# RSS_0_3.net
KiCad netlist of a schematic drawn in EAGLE
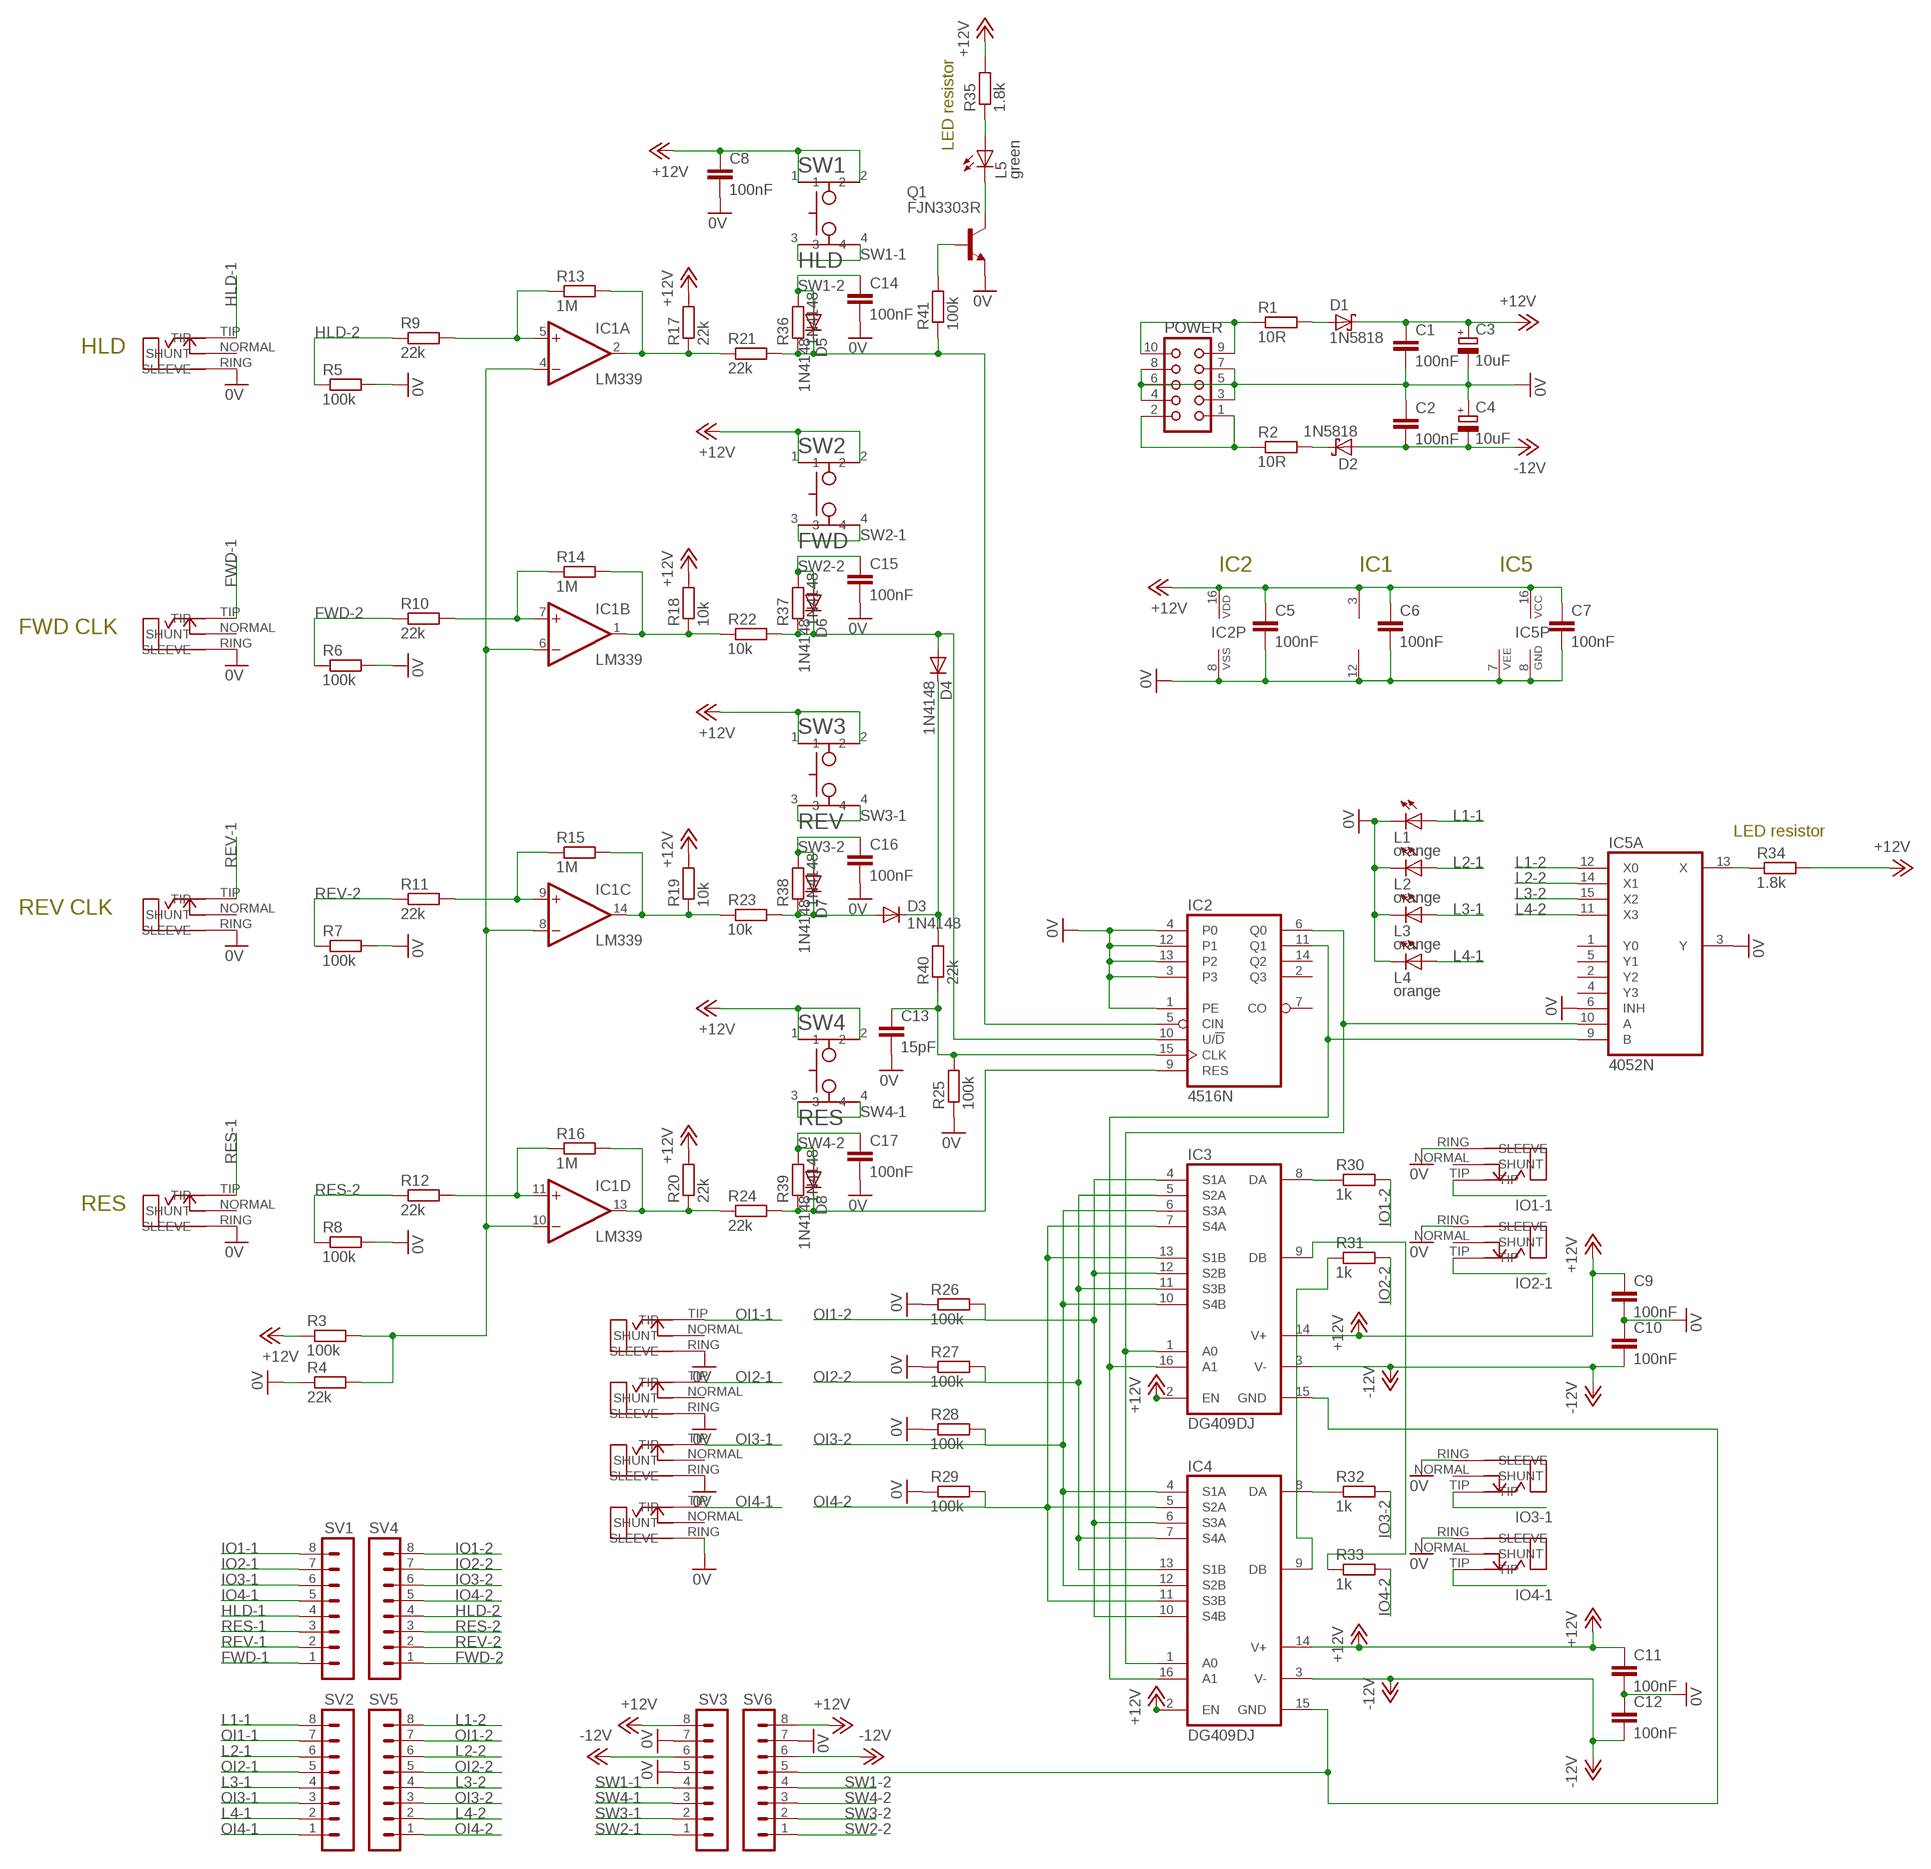
[diagram p0: schematic, sheet 1]

(export (version "E")
  (design (tool "Eeschema 10.0.6"))
  (components
    (comp (ref "C1")
      (value "100nF")
      (footprint "eagle-import:C025-024X044")
      (libsource (lib "eagle-import") (part "C-EU025-024X044"))
    )
    (comp (ref "C2")
      (value "100nF")
      (footprint "eagle-import:C025-024X044")
      (libsource (lib "eagle-import") (part "C-EU025-024X044"))
    )
    (comp (ref "C3")
      (value "10uF")
      (footprint "eagle-import:E2-5")
      (libsource (lib "eagle-import") (part "CPOL-EUE2-5"))
    )
    (comp (ref "C4")
      (value "10uF")
      (footprint "eagle-import:E2-5")
      (libsource (lib "eagle-import") (part "CPOL-EUE2-5"))
    )
    (comp (ref "C5")
      (value "100nF")
      (footprint "eagle-import:C025-024X044")
      (libsource (lib "eagle-import") (part "C-EU025-024X044"))
    )
    (comp (ref "C6")
      (value "100nF")
      (footprint "eagle-import:C025-024X044")
      (libsource (lib "eagle-import") (part "C-EU025-024X044"))
    )
    (comp (ref "C7")
      (value "100nF")
      (footprint "eagle-import:C025-024X044")
      (libsource (lib "eagle-import") (part "C-EU025-024X044"))
    )
    (comp (ref "C8")
      (value "100nF")
      (footprint "eagle-import:C025-024X044")
      (libsource (lib "eagle-import") (part "C-EU025-024X044"))
    )
    (comp (ref "C9")
      (value "100nF")
      (footprint "eagle-import:C025-024X044")
      (libsource (lib "eagle-import") (part "C-EU025-024X044"))
    )
    (comp (ref "C10")
      (value "100nF")
      (footprint "eagle-import:C025-024X044")
      (libsource (lib "eagle-import") (part "C-EU025-024X044"))
    )
    (comp (ref "C11")
      (value "100nF")
      (footprint "eagle-import:C025-024X044")
      (libsource (lib "eagle-import") (part "C-EU025-024X044"))
    )
    (comp (ref "C12")
      (value "100nF")
      (footprint "eagle-import:C025-024X044")
      (libsource (lib "eagle-import") (part "C-EU025-024X044"))
    )
    (comp (ref "C13")
      (value "15pF")
      (footprint "eagle-import:C025-024X044")
      (libsource (lib "eagle-import") (part "C-EU025-024X044"))
    )
    (comp (ref "C14")
      (value "100nF")
      (footprint "eagle-import:C025-024X044")
      (libsource (lib "eagle-import") (part "C-EU025-024X044"))
    )
    (comp (ref "C15")
      (value "100nF")
      (footprint "eagle-import:C025-024X044")
      (libsource (lib "eagle-import") (part "C-EU025-024X044"))
    )
    (comp (ref "C16")
      (value "100nF")
      (footprint "eagle-import:C025-024X044")
      (libsource (lib "eagle-import") (part "C-EU025-024X044"))
    )
    (comp (ref "C17")
      (value "100nF")
      (footprint "eagle-import:C025-024X044")
      (libsource (lib "eagle-import") (part "C-EU025-024X044"))
    )
    (comp (ref "D1")
      (value "1N5818")
      (footprint "eagle-import:DO41-7")
      (libsource (lib "eagle-import") (part "SB130DO-204AL"))
    )
    (comp (ref "D2")
      (value "1N5818")
      (footprint "eagle-import:DO41-7")
      (libsource (lib "eagle-import") (part "SB130DO-204AL"))
    )
    (comp (ref "D3")
      (value "1N4148")
      (footprint "eagle-import:DO35-7")
      (libsource (lib "eagle-import") (part "1N4148DO35-7"))
    )
    (comp (ref "D4")
      (value "1N4148")
      (footprint "eagle-import:DO35-7")
      (libsource (lib "eagle-import") (part "1N4148DO35-7"))
    )
    (comp (ref "D5")
      (value "1N4148")
      (footprint "eagle-import:DO35-7")
      (libsource (lib "eagle-import") (part "1N4148DO35-7"))
    )
    (comp (ref "D6")
      (value "1N4148")
      (footprint "eagle-import:DO35-7")
      (libsource (lib "eagle-import") (part "1N4148DO35-7"))
    )
    (comp (ref "D7")
      (value "1N4148")
      (footprint "eagle-import:DO35-7")
      (libsource (lib "eagle-import") (part "1N4148DO35-7"))
    )
    (comp (ref "D8")
      (value "1N4148")
      (footprint "eagle-import:DO35-7")
      (libsource (lib "eagle-import") (part "1N4148DO35-7"))
    )
    (comp (ref "FWD")
      (value "ERTHENVAR_3.5MM_JACK")
      (footprint "eagle-import:THONKICON")
      (libsource (lib "eagle-import") (part "ERTHENVAR_3.5MM_JACK"))
    )
    (comp (ref "HLD")
      (value "ERTHENVAR_3.5MM_JACK")
      (footprint "eagle-import:THONKICON")
      (libsource (lib "eagle-import") (part "ERTHENVAR_3.5MM_JACK"))
    )
    (comp (ref "I/O1")
      (value "ERTHENVAR_3.5MM_JACK")
      (footprint "eagle-import:THONKICON")
      (libsource (lib "eagle-import") (part "ERTHENVAR_3.5MM_JACK"))
    )
    (comp (ref "I/O2")
      (value "ERTHENVAR_3.5MM_JACK")
      (footprint "eagle-import:THONKICON")
      (libsource (lib "eagle-import") (part "ERTHENVAR_3.5MM_JACK"))
    )
    (comp (ref "I/O3")
      (value "ERTHENVAR_3.5MM_JACK")
      (footprint "eagle-import:THONKICON")
      (libsource (lib "eagle-import") (part "ERTHENVAR_3.5MM_JACK"))
    )
    (comp (ref "I/O4")
      (value "ERTHENVAR_3.5MM_JACK")
      (footprint "eagle-import:THONKICON")
      (libsource (lib "eagle-import") (part "ERTHENVAR_3.5MM_JACK"))
    )
    (comp (ref "IC1")
      (value "LM339")
      (footprint "eagle-import:DIL14")
      (libsource (lib "eagle-import") (part "LM2901N"))
    )
    (comp (ref "IC2")
      (value "4516N")
      (footprint "eagle-import:DIL16")
      (libsource (lib "eagle-import") (part "4516N"))
    )
    (comp (ref "IC3")
      (value "DG409DJ")
      (footprint "eagle-import:DIL16")
      (fields (field (name "MF") "INTERSIL"))
      (libsource (lib "eagle-import") (part "DG409DJ"))
    )
    (comp (ref "IC4")
      (value "DG409DJ")
      (footprint "eagle-import:DIL16")
      (fields (field (name "MF") "INTERSIL"))
      (libsource (lib "eagle-import") (part "DG409DJ"))
    )
    (comp (ref "IC5")
      (value "4052N")
      (footprint "eagle-import:DIL16")
      (libsource (lib "eagle-import") (part "4052N"))
    )
    (comp (ref "L1")
      (value "orange")
      (footprint "eagle-import:LED3MM")
      (libsource (lib "eagle-import") (part "LED3MM"))
    )
    (comp (ref "L2")
      (value "orange")
      (footprint "eagle-import:LED3MM")
      (libsource (lib "eagle-import") (part "LED3MM"))
    )
    (comp (ref "L3")
      (value "orange")
      (footprint "eagle-import:LED3MM")
      (libsource (lib "eagle-import") (part "LED3MM"))
    )
    (comp (ref "L4")
      (value "orange")
      (footprint "eagle-import:LED3MM")
      (libsource (lib "eagle-import") (part "LED3MM"))
    )
    (comp (ref "L5")
      (value "green")
      (footprint "eagle-import:LED3MM")
      (libsource (lib "eagle-import") (part "LED3MM"))
    )
    (comp (ref "O/I1")
      (value "ERTHENVAR_3.5MM_JACK")
      (footprint "eagle-import:THONKICON")
      (libsource (lib "eagle-import") (part "ERTHENVAR_3.5MM_JACK"))
    )
    (comp (ref "O/I2")
      (value "ERTHENVAR_3.5MM_JACK")
      (footprint "eagle-import:THONKICON")
      (libsource (lib "eagle-import") (part "ERTHENVAR_3.5MM_JACK"))
    )
    (comp (ref "O/I3")
      (value "ERTHENVAR_3.5MM_JACK")
      (footprint "eagle-import:THONKICON")
      (libsource (lib "eagle-import") (part "ERTHENVAR_3.5MM_JACK"))
    )
    (comp (ref "O/I4")
      (value "ERTHENVAR_3.5MM_JACK")
      (footprint "eagle-import:THONKICON")
      (libsource (lib "eagle-import") (part "ERTHENVAR_3.5MM_JACK"))
    )
    (comp (ref "POWER")
      (value "CON10L")
      (footprint "eagle-import:CON10L")
      (libsource (lib "eagle-import") (part "CON10L"))
    )
    (comp (ref "Q1")
      (value "FJN3303R")
      (footprint "eagle-import:TO92-LINE")
      (libsource (lib "eagle-import") (part "FJN3303R"))
    )
    (comp (ref "R1")
      (value "10R")
      (footprint "eagle-import:0207_9")
      (libsource (lib "eagle-import") (part "R-EU_0207/10"))
    )
    (comp (ref "R2")
      (value "10R")
      (footprint "eagle-import:0207_9")
      (libsource (lib "eagle-import") (part "R-EU_0207/10"))
    )
    (comp (ref "R3")
      (value "100k")
      (footprint "eagle-import:0207_9")
      (libsource (lib "eagle-import") (part "R-EU_0207/10"))
    )
    (comp (ref "R4")
      (value "22k")
      (footprint "eagle-import:0207_9")
      (libsource (lib "eagle-import") (part "R-EU_0207/10"))
    )
    (comp (ref "R5")
      (value "100k")
      (footprint "eagle-import:0207_9")
      (libsource (lib "eagle-import") (part "R-EU_0207/10"))
    )
    (comp (ref "R6")
      (value "100k")
      (footprint "eagle-import:0207_9")
      (libsource (lib "eagle-import") (part "R-EU_0207/10"))
    )
    (comp (ref "R7")
      (value "100k")
      (footprint "eagle-import:0207_9")
      (libsource (lib "eagle-import") (part "R-EU_0207/10"))
    )
    (comp (ref "R8")
      (value "100k")
      (footprint "eagle-import:0207_9")
      (libsource (lib "eagle-import") (part "R-EU_0207/10"))
    )
    (comp (ref "R9")
      (value "22k")
      (footprint "eagle-import:0207_9")
      (libsource (lib "eagle-import") (part "R-EU_0207/10"))
    )
    (comp (ref "R10")
      (value "22k")
      (footprint "eagle-import:0207_9")
      (libsource (lib "eagle-import") (part "R-EU_0207/10"))
    )
    (comp (ref "R11")
      (value "22k")
      (footprint "eagle-import:0207_9")
      (libsource (lib "eagle-import") (part "R-EU_0207/10"))
    )
    (comp (ref "R12")
      (value "22k")
      (footprint "eagle-import:0207_9")
      (libsource (lib "eagle-import") (part "R-EU_0207/10"))
    )
    (comp (ref "R13")
      (value "1M")
      (footprint "eagle-import:0207_9")
      (libsource (lib "eagle-import") (part "R-EU_0207/10"))
    )
    (comp (ref "R14")
      (value "1M")
      (footprint "eagle-import:0207_9")
      (libsource (lib "eagle-import") (part "R-EU_0207/10"))
    )
    (comp (ref "R15")
      (value "1M")
      (footprint "eagle-import:0207_9")
      (libsource (lib "eagle-import") (part "R-EU_0207/10"))
    )
    (comp (ref "R16")
      (value "1M")
      (footprint "eagle-import:0207_9")
      (libsource (lib "eagle-import") (part "R-EU_0207/10"))
    )
    (comp (ref "R17")
      (value "22k")
      (footprint "eagle-import:0207_9")
      (libsource (lib "eagle-import") (part "R-EU_0207/10"))
    )
    (comp (ref "R18")
      (value "10k")
      (footprint "eagle-import:0207_9")
      (libsource (lib "eagle-import") (part "R-EU_0207/10"))
    )
    (comp (ref "R19")
      (value "10k")
      (footprint "eagle-import:0207_9")
      (libsource (lib "eagle-import") (part "R-EU_0207/10"))
    )
    (comp (ref "R20")
      (value "22k")
      (footprint "eagle-import:0207_9")
      (libsource (lib "eagle-import") (part "R-EU_0207/10"))
    )
    (comp (ref "R21")
      (value "22k")
      (footprint "eagle-import:0207_9")
      (libsource (lib "eagle-import") (part "R-EU_0207/10"))
    )
    (comp (ref "R22")
      (value "10k")
      (footprint "eagle-import:0207_9")
      (libsource (lib "eagle-import") (part "R-EU_0207/10"))
    )
    (comp (ref "R23")
      (value "10k")
      (footprint "eagle-import:0207_9")
      (libsource (lib "eagle-import") (part "R-EU_0207/10"))
    )
    (comp (ref "R24")
      (value "22k")
      (footprint "eagle-import:0207_9")
      (libsource (lib "eagle-import") (part "R-EU_0207/10"))
    )
    (comp (ref "R25")
      (value "100k")
      (footprint "eagle-import:0207_9")
      (libsource (lib "eagle-import") (part "R-EU_0207/10"))
    )
    (comp (ref "R26")
      (value "100k")
      (footprint "eagle-import:0207_9")
      (libsource (lib "eagle-import") (part "R-EU_0207/10"))
    )
    (comp (ref "R27")
      (value "100k")
      (footprint "eagle-import:0207_9")
      (libsource (lib "eagle-import") (part "R-EU_0207/10"))
    )
    (comp (ref "R28")
      (value "100k")
      (footprint "eagle-import:0207_9")
      (libsource (lib "eagle-import") (part "R-EU_0207/10"))
    )
    (comp (ref "R29")
      (value "100k")
      (footprint "eagle-import:0207_9")
      (libsource (lib "eagle-import") (part "R-EU_0207/10"))
    )
    (comp (ref "R30")
      (value "1k")
      (footprint "eagle-import:0207_9")
      (libsource (lib "eagle-import") (part "R-EU_0207/10"))
    )
    (comp (ref "R31")
      (value "1k")
      (footprint "eagle-import:0207_9")
      (libsource (lib "eagle-import") (part "R-EU_0207/10"))
    )
    (comp (ref "R32")
      (value "1k")
      (footprint "eagle-import:0207_9")
      (libsource (lib "eagle-import") (part "R-EU_0207/10"))
    )
    (comp (ref "R33")
      (value "1k")
      (footprint "eagle-import:0207_9")
      (libsource (lib "eagle-import") (part "R-EU_0207/10"))
    )
    (comp (ref "R34")
      (value "1.8k")
      (footprint "eagle-import:0207_9")
      (libsource (lib "eagle-import") (part "R-EU_0207/10"))
    )
    (comp (ref "R35")
      (value "1.8k")
      (footprint "eagle-import:0207_9")
      (libsource (lib "eagle-import") (part "R-EU_0207/10"))
    )
    (comp (ref "R36")
      (value "1N4148")
      (footprint "eagle-import:0207_9")
      (libsource (lib "eagle-import") (part "R-EU_0207/10"))
    )
    (comp (ref "R37")
      (value "1N4148")
      (footprint "eagle-import:0207_9")
      (libsource (lib "eagle-import") (part "R-EU_0207/10"))
    )
    (comp (ref "R38")
      (value "1N4148")
      (footprint "eagle-import:0207_9")
      (libsource (lib "eagle-import") (part "R-EU_0207/10"))
    )
    (comp (ref "R39")
      (value "1N4148")
      (footprint "eagle-import:0207_9")
      (libsource (lib "eagle-import") (part "R-EU_0207/10"))
    )
    (comp (ref "R40")
      (value "22k")
      (footprint "eagle-import:0207_9")
      (libsource (lib "eagle-import") (part "R-EU_0207/10"))
    )
    (comp (ref "R41")
      (value "100k")
      (footprint "eagle-import:0207_9")
      (libsource (lib "eagle-import") (part "R-EU_0207/10"))
    )
    (comp (ref "RES")
      (value "ERTHENVAR_3.5MM_JACK")
      (footprint "eagle-import:THONKICON")
      (libsource (lib "eagle-import") (part "ERTHENVAR_3.5MM_JACK"))
    )
    (comp (ref "REV")
      (value "ERTHENVAR_3.5MM_JACK")
      (footprint "eagle-import:THONKICON")
      (libsource (lib "eagle-import") (part "ERTHENVAR_3.5MM_JACK"))
    )
    (comp (ref "SV1")
      (value "MA08-1")
      (footprint "eagle-import:MA08-1")
      (libsource (lib "eagle-import") (part "MA08-1"))
    )
    (comp (ref "SV2")
      (value "MA08-1")
      (footprint "eagle-import:MA08-1")
      (libsource (lib "eagle-import") (part "MA08-1"))
    )
    (comp (ref "SV3")
      (value "MA08-1")
      (footprint "eagle-import:MA08-1")
      (libsource (lib "eagle-import") (part "MA08-1"))
    )
    (comp (ref "SV4")
      (value "MA08-1")
      (footprint "eagle-import:MA08-1")
      (libsource (lib "eagle-import") (part "MA08-1"))
    )
    (comp (ref "SV5")
      (value "MA08-1")
      (footprint "eagle-import:MA08-1")
      (libsource (lib "eagle-import") (part "MA08-1"))
    )
    (comp (ref "SV6")
      (value "MA08-1")
      (footprint "eagle-import:MA08-1")
      (libsource (lib "eagle-import") (part "MA08-1"))
    )
    (comp (ref "SW1")
      (value "HLD")
      (footprint "eagle-import:TACTILE_ALPS")
      (libsource (lib "eagle-import") (part "TACTILE_ALPS"))
    )
    (comp (ref "SW2")
      (value "FWD")
      (footprint "eagle-import:TACTILE_ALPS")
      (libsource (lib "eagle-import") (part "TACTILE_ALPS"))
    )
    (comp (ref "SW3")
      (value "REV")
      (footprint "eagle-import:TACTILE_ALPS")
      (libsource (lib "eagle-import") (part "TACTILE_ALPS"))
    )
    (comp (ref "SW4")
      (value "RES")
      (footprint "eagle-import:TACTILE_ALPS")
      (libsource (lib "eagle-import") (part "TACTILE_ALPS"))
    )
  )
  (nets
    (net (code "1") (name "+12V") (class "Default")
      (node (ref "C1") (pin "1") (pinfunction "1_1") (pintype "passive"))
      (node (ref "C11") (pin "1") (pinfunction "1_1") (pintype "passive"))
      (node (ref "C3") (pin "+") (pinfunction "+_+") (pintype "passive"))
      (node (ref "C5") (pin "1") (pinfunction "1_1") (pintype "passive"))
      (node (ref "C6") (pin "1") (pinfunction "1_1") (pintype "passive"))
      (node (ref "C7") (pin "1") (pinfunction "1_1") (pintype "passive"))
      (node (ref "C8") (pin "1") (pinfunction "1_1") (pintype "passive"))
      (node (ref "C9") (pin "1") (pinfunction "1_1") (pintype "passive"))
      (node (ref "D1") (pin "C") (pinfunction "C_C") (pintype "passive"))
      (node (ref "IC1") (pin "3") (pinfunction "V+_3") (pintype "power_in"))
      (node (ref "IC2") (pin "16") (pinfunction "VDD_16") (pintype "power_in"))
      (node (ref "IC3") (pin "14") (pinfunction "V+_14") (pintype "power_in"))
      (node (ref "IC3") (pin "2") (pinfunction "EN_2") (pintype "input"))
      (node (ref "IC4") (pin "14") (pinfunction "V+_14") (pintype "power_in"))
      (node (ref "IC4") (pin "2") (pinfunction "EN_2") (pintype "input"))
      (node (ref "IC5") (pin "16") (pinfunction "VCC_16") (pintype "power_in"))
      (node (ref "R17") (pin "2") (pinfunction "2_2") (pintype "passive"))
      (node (ref "R18") (pin "2") (pinfunction "2_2") (pintype "passive"))
      (node (ref "R19") (pin "2") (pinfunction "2_2") (pintype "passive"))
      (node (ref "R20") (pin "2") (pinfunction "2_2") (pintype "passive"))
      (node (ref "R3") (pin "1") (pinfunction "1_1") (pintype "passive"))
      (node (ref "R34") (pin "2") (pinfunction "2_2") (pintype "passive"))
      (node (ref "R35") (pin "2") (pinfunction "2_2") (pintype "passive"))
      (node (ref "SV3") (pin "8") (pinfunction "8_8") (pintype "passive"))
      (node (ref "SV6") (pin "8") (pinfunction "8_8") (pintype "passive"))
      (node (ref "SW1") (pin "1") (pinfunction "1_1") (pintype "bidirectional"))
      (node (ref "SW1") (pin "2") (pinfunction "2_2") (pintype "bidirectional"))
      (node (ref "SW2") (pin "1") (pinfunction "1_1") (pintype "bidirectional"))
      (node (ref "SW2") (pin "2") (pinfunction "2_2") (pintype "bidirectional"))
      (node (ref "SW3") (pin "1") (pinfunction "1_1") (pintype "bidirectional"))
      (node (ref "SW3") (pin "2") (pinfunction "2_2") (pintype "bidirectional"))
      (node (ref "SW4") (pin "1") (pinfunction "1_1") (pintype "bidirectional"))
      (node (ref "SW4") (pin "2") (pinfunction "2_2") (pintype "bidirectional"))
    )
    (net (code "2") (name "-12V") (class "Default")
      (node (ref "C10") (pin "2") (pinfunction "2_2") (pintype "passive"))
      (node (ref "C12") (pin "2") (pinfunction "2_2") (pintype "passive"))
      (node (ref "C2") (pin "2") (pinfunction "2_2") (pintype "passive"))
      (node (ref "C4") (pin "-") (pinfunction "-_-") (pintype "passive"))
      (node (ref "D2") (pin "A") (pinfunction "A_A") (pintype "passive"))
      (node (ref "IC3") (pin "3") (pinfunction "V-_3") (pintype "power_in"))
      (node (ref "IC4") (pin "3") (pinfunction "V-_3") (pintype "power_in"))
      (node (ref "SV3") (pin "6") (pinfunction "6_6") (pintype "passive"))
      (node (ref "SV6") (pin "6") (pinfunction "6_6") (pintype "passive"))
    )
    (net (code "3") (name "/FWD-1") (class "Default")
      (node (ref "FWD") (pin "TIP") (pinfunction "TIP_TIP") (pintype "bidirectional"))
      (node (ref "SV1") (pin "1") (pinfunction "1_1") (pintype "passive"))
    )
    (net (code "4") (name "/FWD-2") (class "Default")
      (node (ref "R10") (pin "1") (pinfunction "1_1") (pintype "passive"))
      (node (ref "R6") (pin "1") (pinfunction "1_1") (pintype "passive"))
      (node (ref "SV4") (pin "1") (pinfunction "1_1") (pintype "passive"))
    )
    (net (code "5") (name "/HLD-1") (class "Default")
      (node (ref "HLD") (pin "TIP") (pinfunction "TIP_TIP") (pintype "bidirectional"))
      (node (ref "SV1") (pin "4") (pinfunction "4_4") (pintype "passive"))
    )
    (net (code "6") (name "/HLD-2") (class "Default")
      (node (ref "R5") (pin "1") (pinfunction "1_1") (pintype "passive"))
      (node (ref "R9") (pin "1") (pinfunction "1_1") (pintype "passive"))
      (node (ref "SV4") (pin "4") (pinfunction "4_4") (pintype "passive"))
    )
    (net (code "7") (name "/IO1-1") (class "Default")
      (node (ref "I/O1") (pin "TIP") (pinfunction "TIP_TIP") (pintype "bidirectional"))
      (node (ref "SV1") (pin "8") (pinfunction "8_8") (pintype "passive"))
    )
    (net (code "8") (name "/IO1-2") (class "Default")
      (node (ref "R30") (pin "2") (pinfunction "2_2") (pintype "passive"))
      (node (ref "SV4") (pin "8") (pinfunction "8_8") (pintype "passive"))
    )
    (net (code "9") (name "/IO2-1") (class "Default")
      (node (ref "I/O2") (pin "TIP") (pinfunction "TIP_TIP") (pintype "bidirectional"))
      (node (ref "SV1") (pin "7") (pinfunction "7_7") (pintype "passive"))
    )
    (net (code "10") (name "/IO2-2") (class "Default")
      (node (ref "R31") (pin "2") (pinfunction "2_2") (pintype "passive"))
      (node (ref "SV4") (pin "7") (pinfunction "7_7") (pintype "passive"))
    )
    (net (code "11") (name "/IO3-1") (class "Default")
      (node (ref "I/O3") (pin "TIP") (pinfunction "TIP_TIP") (pintype "bidirectional"))
      (node (ref "SV1") (pin "6") (pinfunction "6_6") (pintype "passive"))
    )
    (net (code "12") (name "/IO3-2") (class "Default")
      (node (ref "R32") (pin "2") (pinfunction "2_2") (pintype "passive"))
      (node (ref "SV4") (pin "6") (pinfunction "6_6") (pintype "passive"))
    )
    (net (code "13") (name "/IO4-1") (class "Default")
      (node (ref "I/O4") (pin "TIP") (pinfunction "TIP_TIP") (pintype "bidirectional"))
      (node (ref "SV1") (pin "5") (pinfunction "5_5") (pintype "passive"))
    )
    (net (code "14") (name "/IO4-2") (class "Default")
      (node (ref "R33") (pin "2") (pinfunction "2_2") (pintype "passive"))
      (node (ref "SV4") (pin "5") (pinfunction "5_5") (pintype "passive"))
    )
    (net (code "15") (name "/L1-1") (class "Default")
      (node (ref "L1") (pin "A") (pinfunction "A_A") (pintype "passive"))
      (node (ref "SV2") (pin "8") (pinfunction "8_8") (pintype "passive"))
    )
    (net (code "16") (name "/L1-2") (class "Default")
      (node (ref "IC5") (pin "12") (pinfunction "X0_12") (pintype "bidirectional"))
      (node (ref "SV5") (pin "8") (pinfunction "8_8") (pintype "passive"))
    )
    (net (code "17") (name "/L2-1") (class "Default")
      (node (ref "L2") (pin "A") (pinfunction "A_A") (pintype "passive"))
      (node (ref "SV2") (pin "6") (pinfunction "6_6") (pintype "passive"))
    )
    (net (code "18") (name "/L2-2") (class "Default")
      (node (ref "IC5") (pin "14") (pinfunction "X1_14") (pintype "bidirectional"))
      (node (ref "SV5") (pin "6") (pinfunction "6_6") (pintype "passive"))
    )
    (net (code "19") (name "/L3-1") (class "Default")
      (node (ref "L3") (pin "A") (pinfunction "A_A") (pintype "passive"))
      (node (ref "SV2") (pin "4") (pinfunction "4_4") (pintype "passive"))
    )
    (net (code "20") (name "/L3-2") (class "Default")
      (node (ref "IC5") (pin "15") (pinfunction "X2_15") (pintype "bidirectional"))
      (node (ref "SV5") (pin "4") (pinfunction "4_4") (pintype "passive"))
    )
    (net (code "21") (name "/L4-1") (class "Default")
      (node (ref "L4") (pin "A") (pinfunction "A_A") (pintype "passive"))
      (node (ref "SV2") (pin "2") (pinfunction "2_2") (pintype "passive"))
    )
    (net (code "22") (name "/L4-2") (class "Default")
      (node (ref "IC5") (pin "11") (pinfunction "X3_11") (pintype "bidirectional"))
      (node (ref "SV5") (pin "2") (pinfunction "2_2") (pintype "passive"))
    )
    (net (code "23") (name "/OI1-1") (class "Default")
      (node (ref "O/I1") (pin "TIP") (pinfunction "TIP_TIP") (pintype "bidirectional"))
      (node (ref "SV2") (pin "7") (pinfunction "7_7") (pintype "passive"))
    )
    (net (code "24") (name "/OI1-2") (class "Default")
      (node (ref "IC3") (pin "12") (pinfunction "S2B_12") (pintype "passive"))
      (node (ref "IC3") (pin "4") (pinfunction "S1A_4") (pintype "passive"))
      (node (ref "IC4") (pin "10") (pinfunction "S4B_10") (pintype "passive"))
      (node (ref "IC4") (pin "6") (pinfunction "S3A_6") (pintype "passive"))
      (node (ref "R26") (pin "2") (pinfunction "2_2") (pintype "passive"))
      (node (ref "SV5") (pin "7") (pinfunction "7_7") (pintype "passive"))
    )
    (net (code "25") (name "/OI2-1") (class "Default")
      (node (ref "O/I2") (pin "TIP") (pinfunction "TIP_TIP") (pintype "bidirectional"))
      (node (ref "SV2") (pin "5") (pinfunction "5_5") (pintype "passive"))
    )
    (net (code "26") (name "/OI2-2") (class "Default")
      (node (ref "IC3") (pin "11") (pinfunction "S3B_11") (pintype "passive"))
      (node (ref "IC3") (pin "5") (pinfunction "S2A_5") (pintype "passive"))
      (node (ref "IC4") (pin "13") (pinfunction "S1B_13") (pintype "passive"))
      (node (ref "IC4") (pin "7") (pinfunction "S4A_7") (pintype "passive"))
      (node (ref "R27") (pin "2") (pinfunction "2_2") (pintype "passive"))
      (node (ref "SV5") (pin "5") (pinfunction "5_5") (pintype "passive"))
    )
    (net (code "27") (name "/OI3-1") (class "Default")
      (node (ref "O/I3") (pin "TIP") (pinfunction "TIP_TIP") (pintype "bidirectional"))
      (node (ref "SV2") (pin "3") (pinfunction "3_3") (pintype "passive"))
    )
    (net (code "28") (name "/OI3-2") (class "Default")
      (node (ref "IC3") (pin "10") (pinfunction "S4B_10") (pintype "passive"))
      (node (ref "IC3") (pin "6") (pinfunction "S3A_6") (pintype "passive"))
      (node (ref "IC4") (pin "12") (pinfunction "S2B_12") (pintype "passive"))
      (node (ref "IC4") (pin "4") (pinfunction "S1A_4") (pintype "passive"))
      (node (ref "R28") (pin "2") (pinfunction "2_2") (pintype "passive"))
      (node (ref "SV5") (pin "3") (pinfunction "3_3") (pintype "passive"))
    )
    (net (code "29") (name "/OI4-1") (class "Default")
      (node (ref "O/I4") (pin "TIP") (pinfunction "TIP_TIP") (pintype "bidirectional"))
      (node (ref "SV2") (pin "1") (pinfunction "1_1") (pintype "passive"))
    )
    (net (code "30") (name "/OI4-2") (class "Default")
      (node (ref "IC3") (pin "13") (pinfunction "S1B_13") (pintype "passive"))
      (node (ref "IC3") (pin "7") (pinfunction "S4A_7") (pintype "passive"))
      (node (ref "IC4") (pin "11") (pinfunction "S3B_11") (pintype "passive"))
      (node (ref "IC4") (pin "5") (pinfunction "S2A_5") (pintype "passive"))
      (node (ref "R29") (pin "2") (pinfunction "2_2") (pintype "passive"))
      (node (ref "SV5") (pin "1") (pinfunction "1_1") (pintype "passive"))
    )
    (net (code "31") (name "/RES-1") (class "Default")
      (node (ref "RES") (pin "TIP") (pinfunction "TIP_TIP") (pintype "bidirectional"))
      (node (ref "SV1") (pin "3") (pinfunction "3_3") (pintype "passive"))
    )
    (net (code "32") (name "/RES-2") (class "Default")
      (node (ref "R12") (pin "1") (pinfunction "1_1") (pintype "passive"))
      (node (ref "R8") (pin "1") (pinfunction "1_1") (pintype "passive"))
      (node (ref "SV4") (pin "3") (pinfunction "3_3") (pintype "passive"))
    )
    (net (code "33") (name "/REV-1") (class "Default")
      (node (ref "REV") (pin "TIP") (pinfunction "TIP_TIP") (pintype "bidirectional"))
      (node (ref "SV1") (pin "2") (pinfunction "2_2") (pintype "passive"))
    )
    (net (code "34") (name "/REV-2") (class "Default")
      (node (ref "R11") (pin "1") (pinfunction "1_1") (pintype "passive"))
      (node (ref "R7") (pin "1") (pinfunction "1_1") (pintype "passive"))
      (node (ref "SV4") (pin "2") (pinfunction "2_2") (pintype "passive"))
    )
    (net (code "35") (name "/SW1-1") (class "Default")
      (node (ref "SV3") (pin "4") (pinfunction "4_4") (pintype "passive"))
      (node (ref "SW1") (pin "3") (pinfunction "3_3") (pintype "bidirectional"))
      (node (ref "SW1") (pin "4") (pinfunction "4_4") (pintype "bidirectional"))
    )
    (net (code "36") (name "/SW1-2") (class "Default")
      (node (ref "C14") (pin "1") (pinfunction "1_1") (pintype "passive"))
      (node (ref "D5") (pin "A") (pinfunction "A_A") (pintype "passive"))
      (node (ref "R36") (pin "2") (pinfunction "2_2") (pintype "passive"))
      (node (ref "SV6") (pin "4") (pinfunction "4_4") (pintype "passive"))
    )
    (net (code "37") (name "/SW2-1") (class "Default")
      (node (ref "SV3") (pin "1") (pinfunction "1_1") (pintype "passive"))
      (node (ref "SW2") (pin "3") (pinfunction "3_3") (pintype "bidirectional"))
      (node (ref "SW2") (pin "4") (pinfunction "4_4") (pintype "bidirectional"))
    )
    (net (code "38") (name "/SW2-2") (class "Default")
      (node (ref "C15") (pin "1") (pinfunction "1_1") (pintype "passive"))
      (node (ref "D6") (pin "A") (pinfunction "A_A") (pintype "passive"))
      (node (ref "R37") (pin "2") (pinfunction "2_2") (pintype "passive"))
      (node (ref "SV6") (pin "1") (pinfunction "1_1") (pintype "passive"))
    )
    (net (code "39") (name "/SW3-1") (class "Default")
      (node (ref "SV3") (pin "2") (pinfunction "2_2") (pintype "passive"))
      (node (ref "SW3") (pin "3") (pinfunction "3_3") (pintype "bidirectional"))
      (node (ref "SW3") (pin "4") (pinfunction "4_4") (pintype "bidirectional"))
    )
    (net (code "40") (name "/SW3-2") (class "Default")
      (node (ref "C16") (pin "1") (pinfunction "1_1") (pintype "passive"))
      (node (ref "D7") (pin "A") (pinfunction "A_A") (pintype "passive"))
      (node (ref "R38") (pin "2") (pinfunction "2_2") (pintype "passive"))
      (node (ref "SV6") (pin "2") (pinfunction "2_2") (pintype "passive"))
    )
    (net (code "41") (name "/SW4-1") (class "Default")
      (node (ref "SV3") (pin "3") (pinfunction "3_3") (pintype "passive"))
      (node (ref "SW4") (pin "3") (pinfunction "3_3") (pintype "bidirectional"))
      (node (ref "SW4") (pin "4") (pinfunction "4_4") (pintype "bidirectional"))
    )
    (net (code "42") (name "/SW4-2") (class "Default")
      (node (ref "C17") (pin "1") (pinfunction "1_1") (pintype "passive"))
      (node (ref "D8") (pin "A") (pinfunction "A_A") (pintype "passive"))
      (node (ref "R39") (pin "2") (pinfunction "2_2") (pintype "passive"))
      (node (ref "SV6") (pin "3") (pinfunction "3_3") (pintype "passive"))
    )
    (net (code "43") (name "0V") (class "Default")
      (node (ref "C1") (pin "2") (pinfunction "2_2") (pintype "passive"))
      (node (ref "C10") (pin "1") (pinfunction "1_1") (pintype "passive"))
      (node (ref "C11") (pin "2") (pinfunction "2_2") (pintype "passive"))
      (node (ref "C12") (pin "1") (pinfunction "1_1") (pintype "passive"))
      (node (ref "C13") (pin "2") (pinfunction "2_2") (pintype "passive"))
      (node (ref "C14") (pin "2") (pinfunction "2_2") (pintype "passive"))
      (node (ref "C15") (pin "2") (pinfunction "2_2") (pintype "passive"))
      (node (ref "C16") (pin "2") (pinfunction "2_2") (pintype "passive"))
      (node (ref "C17") (pin "2") (pinfunction "2_2") (pintype "passive"))
      (node (ref "C2") (pin "1") (pinfunction "1_1") (pintype "passive"))
      (node (ref "C3") (pin "-") (pinfunction "-_-") (pintype "passive"))
      (node (ref "C4") (pin "+") (pinfunction "+_+") (pintype "passive"))
      (node (ref "C5") (pin "2") (pinfunction "2_2") (pintype "passive"))
      (node (ref "C6") (pin "2") (pinfunction "2_2") (pintype "passive"))
      (node (ref "C7") (pin "2") (pinfunction "2_2") (pintype "passive"))
      (node (ref "C8") (pin "2") (pinfunction "2_2") (pintype "passive"))
      (node (ref "C9") (pin "2") (pinfunction "2_2") (pintype "passive"))
      (node (ref "FWD") (pin "RING") (pinfunction "SLEEVE_RING") (pintype "bidirectional"))
      (node (ref "HLD") (pin "RING") (pinfunction "SLEEVE_RING") (pintype "bidirectional"))
      (node (ref "I/O1") (pin "RING") (pinfunction "SLEEVE_RING") (pintype "bidirectional"))
      (node (ref "I/O2") (pin "RING") (pinfunction "SLEEVE_RING") (pintype "bidirectional"))
      (node (ref "I/O3") (pin "RING") (pinfunction "SLEEVE_RING") (pintype "bidirectional"))
      (node (ref "I/O4") (pin "RING") (pinfunction "SLEEVE_RING") (pintype "bidirectional"))
      (node (ref "IC1") (pin "12") (pinfunction "V-_12") (pintype "power_in"))
      (node (ref "IC2") (pin "1") (pinfunction "PE_1") (pintype "input"))
      (node (ref "IC2") (pin "12") (pinfunction "P1_12") (pintype "input"))
      (node (ref "IC2") (pin "13") (pinfunction "P2_13") (pintype "input"))
      (node (ref "IC2") (pin "3") (pinfunction "P3_3") (pintype "input"))
      (node (ref "IC2") (pin "4") (pinfunction "P0_4") (pintype "input"))
      (node (ref "IC2") (pin "8") (pinfunction "VSS_8") (pintype "power_in"))
      (node (ref "IC5") (pin "3") (pinfunction "Y_3") (pintype "bidirectional"))
      (node (ref "IC5") (pin "6") (pinfunction "INH_6") (pintype "input"))
      (node (ref "IC5") (pin "7") (pinfunction "VEE_7") (pintype "power_in"))
      (node (ref "IC5") (pin "8") (pinfunction "GND_8") (pintype "power_in"))
      (node (ref "L1") (pin "K") (pinfunction "C_K") (pintype "passive"))
      (node (ref "L2") (pin "K") (pinfunction "C_K") (pintype "passive"))
      (node (ref "L3") (pin "K") (pinfunction "C_K") (pintype "passive"))
      (node (ref "L4") (pin "K") (pinfunction "C_K") (pintype "passive"))
      (node (ref "O/I1") (pin "RING") (pinfunction "SLEEVE_RING") (pintype "bidirectional"))
      (node (ref "O/I2") (pin "RING") (pinfunction "SLEEVE_RING") (pintype "bidirectional"))
      (node (ref "O/I3") (pin "RING") (pinfunction "SLEEVE_RING") (pintype "bidirectional"))
      (node (ref "O/I4") (pin "RING") (pinfunction "SLEEVE_RING") (pintype "bidirectional"))
      (node (ref "POWER") (pin "3") (pinfunction "3_3") (pintype "passive"))
      (node (ref "POWER") (pin "4") (pinfunction "4_4") (pintype "passive"))
      (node (ref "POWER") (pin "5") (pinfunction "5_5") (pintype "passive"))
      (node (ref "POWER") (pin "6") (pinfunction "6_6") (pintype "passive"))
      (node (ref "POWER") (pin "7") (pinfunction "7_7") (pintype "passive"))
      (node (ref "POWER") (pin "8") (pinfunction "8_8") (pintype "passive"))
      (node (ref "Q1") (pin "3") (pinfunction "E_3") (pintype "passive"))
      (node (ref "R25") (pin "1") (pinfunction "1_1") (pintype "passive"))
      (node (ref "R26") (pin "1") (pinfunction "1_1") (pintype "passive"))
      (node (ref "R27") (pin "1") (pinfunction "1_1") (pintype "passive"))
      (node (ref "R28") (pin "1") (pinfunction "1_1") (pintype "passive"))
      (node (ref "R29") (pin "1") (pinfunction "1_1") (pintype "passive"))
      (node (ref "R4") (pin "1") (pinfunction "1_1") (pintype "passive"))
      (node (ref "R5") (pin "2") (pinfunction "2_2") (pintype "passive"))
      (node (ref "R6") (pin "2") (pinfunction "2_2") (pintype "passive"))
      (node (ref "R7") (pin "2") (pinfunction "2_2") (pintype "passive"))
      (node (ref "R8") (pin "2") (pinfunction "2_2") (pintype "passive"))
      (node (ref "RES") (pin "RING") (pinfunction "SLEEVE_RING") (pintype "bidirectional"))
      (node (ref "REV") (pin "RING") (pinfunction "SLEEVE_RING") (pintype "bidirectional"))
      (node (ref "SV3") (pin "5") (pinfunction "5_5") (pintype "passive"))
      (node (ref "SV3") (pin "7") (pinfunction "7_7") (pintype "passive"))
      (node (ref "SV6") (pin "7") (pinfunction "7_7") (pintype "passive"))
    )
    (net (code "44") (name "Net-(D1-PadA)") (class "Default")
      (node (ref "D1") (pin "A") (pinfunction "A_A") (pintype "passive"))
      (node (ref "R1") (pin "2") (pinfunction "2_2") (pintype "passive"))
    )
    (net (code "45") (name "Net-(D2-PadC)") (class "Default")
      (node (ref "D2") (pin "C") (pinfunction "C_C") (pintype "passive"))
      (node (ref "R2") (pin "2") (pinfunction "2_2") (pintype "passive"))
    )
    (net (code "46") (name "Net-(D3-PadA)") (class "Default")
      (node (ref "D3") (pin "A") (pinfunction "A_A") (pintype "passive"))
      (node (ref "D7") (pin "C") (pinfunction "C_C") (pintype "passive"))
      (node (ref "R23") (pin "2") (pinfunction "2_2") (pintype "passive"))
      (node (ref "R38") (pin "1") (pinfunction "1_1") (pintype "passive"))
    )
    (net (code "47") (name "Net-(D3-PadC)") (class "Default")
      (node (ref "D3") (pin "C") (pinfunction "C_C") (pintype "passive"))
      (node (ref "D4") (pin "C") (pinfunction "C_C") (pintype "passive"))
      (node (ref "R40") (pin "2") (pinfunction "2_2") (pintype "passive"))
    )
    (net (code "48") (name "Net-(IC1A-+IN)") (class "Default")
      (node (ref "IC1") (pin "5") (pinfunction "+IN_5") (pintype "input"))
      (node (ref "R13") (pin "1") (pinfunction "1_1") (pintype "passive"))
      (node (ref "R9") (pin "2") (pinfunction "2_2") (pintype "passive"))
    )
    (net (code "49") (name "Net-(IC1A--IN)") (class "Default")
      (node (ref "IC1") (pin "10") (pinfunction "-IN_10") (pintype "input"))
      (node (ref "IC1") (pin "4") (pinfunction "-IN_4") (pintype "input"))
      (node (ref "IC1") (pin "6") (pinfunction "-IN_6") (pintype "input"))
      (node (ref "IC1") (pin "8") (pinfunction "-IN_8") (pintype "input"))
      (node (ref "R3") (pin "2") (pinfunction "2_2") (pintype "passive"))
      (node (ref "R4") (pin "2") (pinfunction "2_2") (pintype "passive"))
    )
    (net (code "50") (name "Net-(IC1A-OUT)") (class "Default")
      (node (ref "IC1") (pin "2") (pinfunction "OUT_2") (pintype "output"))
      (node (ref "R13") (pin "2") (pinfunction "2_2") (pintype "passive"))
      (node (ref "R17") (pin "1") (pinfunction "1_1") (pintype "passive"))
      (node (ref "R21") (pin "1") (pinfunction "1_1") (pintype "passive"))
    )
    (net (code "51") (name "Net-(IC1B-+IN)") (class "Default")
      (node (ref "IC1") (pin "7") (pinfunction "+IN_7") (pintype "input"))
      (node (ref "R10") (pin "2") (pinfunction "2_2") (pintype "passive"))
      (node (ref "R14") (pin "1") (pinfunction "1_1") (pintype "passive"))
    )
    (net (code "52") (name "Net-(IC1B-OUT)") (class "Default")
      (node (ref "IC1") (pin "1") (pinfunction "OUT_1") (pintype "output"))
      (node (ref "R14") (pin "2") (pinfunction "2_2") (pintype "passive"))
      (node (ref "R18") (pin "1") (pinfunction "1_1") (pintype "passive"))
      (node (ref "R22") (pin "1") (pinfunction "1_1") (pintype "passive"))
    )
    (net (code "53") (name "Net-(IC1C-+IN)") (class "Default")
      (node (ref "IC1") (pin "9") (pinfunction "+IN_9") (pintype "input"))
      (node (ref "R11") (pin "2") (pinfunction "2_2") (pintype "passive"))
      (node (ref "R15") (pin "1") (pinfunction "1_1") (pintype "passive"))
    )
    (net (code "54") (name "Net-(IC1C-OUT)") (class "Default")
      (node (ref "IC1") (pin "14") (pinfunction "OUT_14") (pintype "output"))
      (node (ref "R15") (pin "2") (pinfunction "2_2") (pintype "passive"))
      (node (ref "R19") (pin "1") (pinfunction "1_1") (pintype "passive"))
      (node (ref "R23") (pin "1") (pinfunction "1_1") (pintype "passive"))
    )
    (net (code "55") (name "Net-(IC1D-+IN)") (class "Default")
      (node (ref "IC1") (pin "11") (pinfunction "+IN_11") (pintype "input"))
      (node (ref "R12") (pin "2") (pinfunction "2_2") (pintype "passive"))
      (node (ref "R16") (pin "1") (pinfunction "1_1") (pintype "passive"))
    )
    (net (code "56") (name "Net-(IC1D-OUT)") (class "Default")
      (node (ref "IC1") (pin "13") (pinfunction "OUT_13") (pintype "output"))
      (node (ref "R16") (pin "2") (pinfunction "2_2") (pintype "passive"))
      (node (ref "R20") (pin "1") (pinfunction "1_1") (pintype "passive"))
      (node (ref "R24") (pin "1") (pinfunction "1_1") (pintype "passive"))
    )
    (net (code "57") (name "Net-(IC2A-CIN)") (class "Default")
      (node (ref "D5") (pin "C") (pinfunction "C_C") (pintype "passive"))
      (node (ref "IC2") (pin "5") (pinfunction "CIN_5") (pintype "input"))
      (node (ref "R21") (pin "2") (pinfunction "2_2") (pintype "passive"))
      (node (ref "R36") (pin "1") (pinfunction "1_1") (pintype "passive"))
      (node (ref "R41") (pin "1") (pinfunction "1_1") (pintype "passive"))
    )
    (net (code "58") (name "Net-(IC2A-CLK)") (class "Default")
      (node (ref "C13") (pin "1") (pinfunction "1_1") (pintype "passive"))
      (node (ref "IC2") (pin "15") (pinfunction "CLK_15") (pintype "input"))
      (node (ref "R25") (pin "2") (pinfunction "2_2") (pintype "passive"))
      (node (ref "R40") (pin "1") (pinfunction "1_1") (pintype "passive"))
    )
    (net (code "59") (name "Net-(IC2A-Q0)") (class "Default")
      (node (ref "IC2") (pin "6") (pinfunction "Q0_6") (pintype "output"))
      (node (ref "IC3") (pin "1") (pinfunction "A0_1") (pintype "input"))
      (node (ref "IC4") (pin "1") (pinfunction "A0_1") (pintype "input"))
      (node (ref "IC5") (pin "10") (pinfunction "A_10") (pintype "input"))
    )
    (net (code "60") (name "Net-(IC2A-Q1)") (class "Default")
      (node (ref "IC2") (pin "11") (pinfunction "Q1_11") (pintype "output"))
      (node (ref "IC3") (pin "16") (pinfunction "A1_16") (pintype "input"))
      (node (ref "IC4") (pin "16") (pinfunction "A1_16") (pintype "input"))
      (node (ref "IC5") (pin "9") (pinfunction "B_9") (pintype "input"))
    )
    (net (code "61") (name "Net-(IC2A-RES)") (class "Default")
      (node (ref "D8") (pin "C") (pinfunction "C_C") (pintype "passive"))
      (node (ref "IC2") (pin "9") (pinfunction "RES_9") (pintype "input"))
      (node (ref "R24") (pin "2") (pinfunction "2_2") (pintype "passive"))
      (node (ref "R39") (pin "1") (pinfunction "1_1") (pintype "passive"))
    )
    (net (code "62") (name "Net-(IC2A-U{slash}~{D})") (class "Default")
      (node (ref "D4") (pin "A") (pinfunction "A_A") (pintype "passive"))
      (node (ref "D6") (pin "C") (pinfunction "C_C") (pintype "passive"))
      (node (ref "IC2") (pin "10") (pinfunction "U/~{D}_10") (pintype "input"))
      (node (ref "R22") (pin "2") (pinfunction "2_2") (pintype "passive"))
      (node (ref "R37") (pin "1") (pinfunction "1_1") (pintype "passive"))
    )
    (net (code "63") (name "Net-(IC3-DA)") (class "Default")
      (node (ref "IC3") (pin "8") (pinfunction "DA_8") (pintype "passive"))
      (node (ref "R30") (pin "1") (pinfunction "1_1") (pintype "passive"))
    )
    (net (code "64") (name "Net-(IC3-DB)") (class "Default")
      (node (ref "IC3") (pin "9") (pinfunction "DB_9") (pintype "passive"))
      (node (ref "R33") (pin "1") (pinfunction "1_1") (pintype "passive"))
    )
    (net (code "65") (name "Net-(IC3-GND)") (class "Default")
      (node (ref "IC3") (pin "15") (pinfunction "GND_15") (pintype "power_in"))
      (node (ref "IC4") (pin "15") (pinfunction "GND_15") (pintype "power_in"))
      (node (ref "SV6") (pin "5") (pinfunction "5_5") (pintype "passive"))
    )
    (net (code "66") (name "Net-(IC4-DA)") (class "Default")
      (node (ref "IC4") (pin "8") (pinfunction "DA_8") (pintype "passive"))
      (node (ref "R32") (pin "1") (pinfunction "1_1") (pintype "passive"))
    )
    (net (code "67") (name "Net-(IC4-DB)") (class "Default")
      (node (ref "IC4") (pin "9") (pinfunction "DB_9") (pintype "passive"))
      (node (ref "R31") (pin "1") (pinfunction "1_1") (pintype "passive"))
    )
    (net (code "68") (name "Net-(IC5A-X)") (class "Default")
      (node (ref "IC5") (pin "13") (pinfunction "X_13") (pintype "bidirectional"))
      (node (ref "R34") (pin "1") (pinfunction "1_1") (pintype "passive"))
    )
    (net (code "69") (name "Net-(L5-C)") (class "Default")
      (node (ref "L5") (pin "K") (pinfunction "C_K") (pintype "passive"))
      (node (ref "Q1") (pin "2") (pinfunction "C_2") (pintype "passive"))
    )
    (net (code "70") (name "Net-(L5-PadA)") (class "Default")
      (node (ref "L5") (pin "A") (pinfunction "A_A") (pintype "passive"))
      (node (ref "R35") (pin "1") (pinfunction "1_1") (pintype "passive"))
    )
    (net (code "71") (name "Net-(POWER-Pad1)") (class "Default")
      (node (ref "POWER") (pin "1") (pinfunction "1_1") (pintype "passive"))
      (node (ref "POWER") (pin "2") (pinfunction "2_2") (pintype "passive"))
      (node (ref "R2") (pin "1") (pinfunction "1_1") (pintype "passive"))
    )
    (net (code "72") (name "Net-(POWER-Pad10)") (class "Default")
      (node (ref "POWER") (pin "10") (pinfunction "10_10") (pintype "passive"))
      (node (ref "POWER") (pin "9") (pinfunction "9_9") (pintype "passive"))
      (node (ref "R1") (pin "1") (pinfunction "1_1") (pintype "passive"))
    )
    (net (code "73") (name "Net-(Q1-B)") (class "Default")
      (node (ref "Q1") (pin "1") (pinfunction "B_1") (pintype "passive"))
      (node (ref "R41") (pin "2") (pinfunction "2_2") (pintype "passive"))
    )
    (net (code "74") (name "unconnected-(FWD-SHUNT-PadNORMAL)") (class "Default")
      (node (ref "FWD") (pin "NORMAL") (pinfunction "SHUNT_NORMAL") (pintype "bidirectional"))
    )
    (net (code "75") (name "unconnected-(HLD-SHUNT-PadNORMAL)") (class "Default")
      (node (ref "HLD") (pin "NORMAL") (pinfunction "SHUNT_NORMAL") (pintype "bidirectional"))
    )
    (net (code "76") (name "unconnected-(I/O1-SHUNT-PadNORMAL)") (class "Default")
      (node (ref "I/O1") (pin "NORMAL") (pinfunction "SHUNT_NORMAL") (pintype "bidirectional"))
    )
    (net (code "77") (name "unconnected-(I/O2-SHUNT-PadNORMAL)") (class "Default")
      (node (ref "I/O2") (pin "NORMAL") (pinfunction "SHUNT_NORMAL") (pintype "bidirectional"))
    )
    (net (code "78") (name "unconnected-(I/O3-SHUNT-PadNORMAL)") (class "Default")
      (node (ref "I/O3") (pin "NORMAL") (pinfunction "SHUNT_NORMAL") (pintype "bidirectional"))
    )
    (net (code "79") (name "unconnected-(I/O4-SHUNT-PadNORMAL)") (class "Default")
      (node (ref "I/O4") (pin "NORMAL") (pinfunction "SHUNT_NORMAL") (pintype "bidirectional"))
    )
    (net (code "80") (name "unconnected-(IC2A-CO-Pad7)") (class "Default")
      (node (ref "IC2") (pin "7") (pinfunction "CO_7") (pintype "output"))
    )
    (net (code "81") (name "unconnected-(IC2A-Q2-Pad14)") (class "Default")
      (node (ref "IC2") (pin "14") (pinfunction "Q2_14") (pintype "output"))
    )
    (net (code "82") (name "unconnected-(IC2A-Q3-Pad2)") (class "Default")
      (node (ref "IC2") (pin "2") (pinfunction "Q3_2") (pintype "output"))
    )
    (net (code "83") (name "unconnected-(IC5A-Y0-Pad1)") (class "Default")
      (node (ref "IC5") (pin "1") (pinfunction "Y0_1") (pintype "bidirectional"))
    )
    (net (code "84") (name "unconnected-(IC5A-Y1-Pad5)") (class "Default")
      (node (ref "IC5") (pin "5") (pinfunction "Y1_5") (pintype "bidirectional"))
    )
    (net (code "85") (name "unconnected-(IC5A-Y2-Pad2)") (class "Default")
      (node (ref "IC5") (pin "2") (pinfunction "Y2_2") (pintype "bidirectional"))
    )
    (net (code "86") (name "unconnected-(IC5A-Y3-Pad4)") (class "Default")
      (node (ref "IC5") (pin "4") (pinfunction "Y3_4") (pintype "bidirectional"))
    )
    (net (code "87") (name "unconnected-(O/I1-SHUNT-PadNORMAL)") (class "Default")
      (node (ref "O/I1") (pin "NORMAL") (pinfunction "SHUNT_NORMAL") (pintype "bidirectional"))
    )
    (net (code "88") (name "unconnected-(O/I2-SHUNT-PadNORMAL)") (class "Default")
      (node (ref "O/I2") (pin "NORMAL") (pinfunction "SHUNT_NORMAL") (pintype "bidirectional"))
    )
    (net (code "89") (name "unconnected-(O/I3-SHUNT-PadNORMAL)") (class "Default")
      (node (ref "O/I3") (pin "NORMAL") (pinfunction "SHUNT_NORMAL") (pintype "bidirectional"))
    )
    (net (code "90") (name "unconnected-(O/I4-SHUNT-PadNORMAL)") (class "Default")
      (node (ref "O/I4") (pin "NORMAL") (pinfunction "SHUNT_NORMAL") (pintype "bidirectional"))
    )
    (net (code "91") (name "unconnected-(RES-SHUNT-PadNORMAL)") (class "Default")
      (node (ref "RES") (pin "NORMAL") (pinfunction "SHUNT_NORMAL") (pintype "bidirectional"))
    )
    (net (code "92") (name "unconnected-(REV-SHUNT-PadNORMAL)") (class "Default")
      (node (ref "REV") (pin "NORMAL") (pinfunction "SHUNT_NORMAL") (pintype "bidirectional"))
    )
  )
)
